# Hooly_2_023.net
KiCad netlist of a schematic drawn in EAGLE
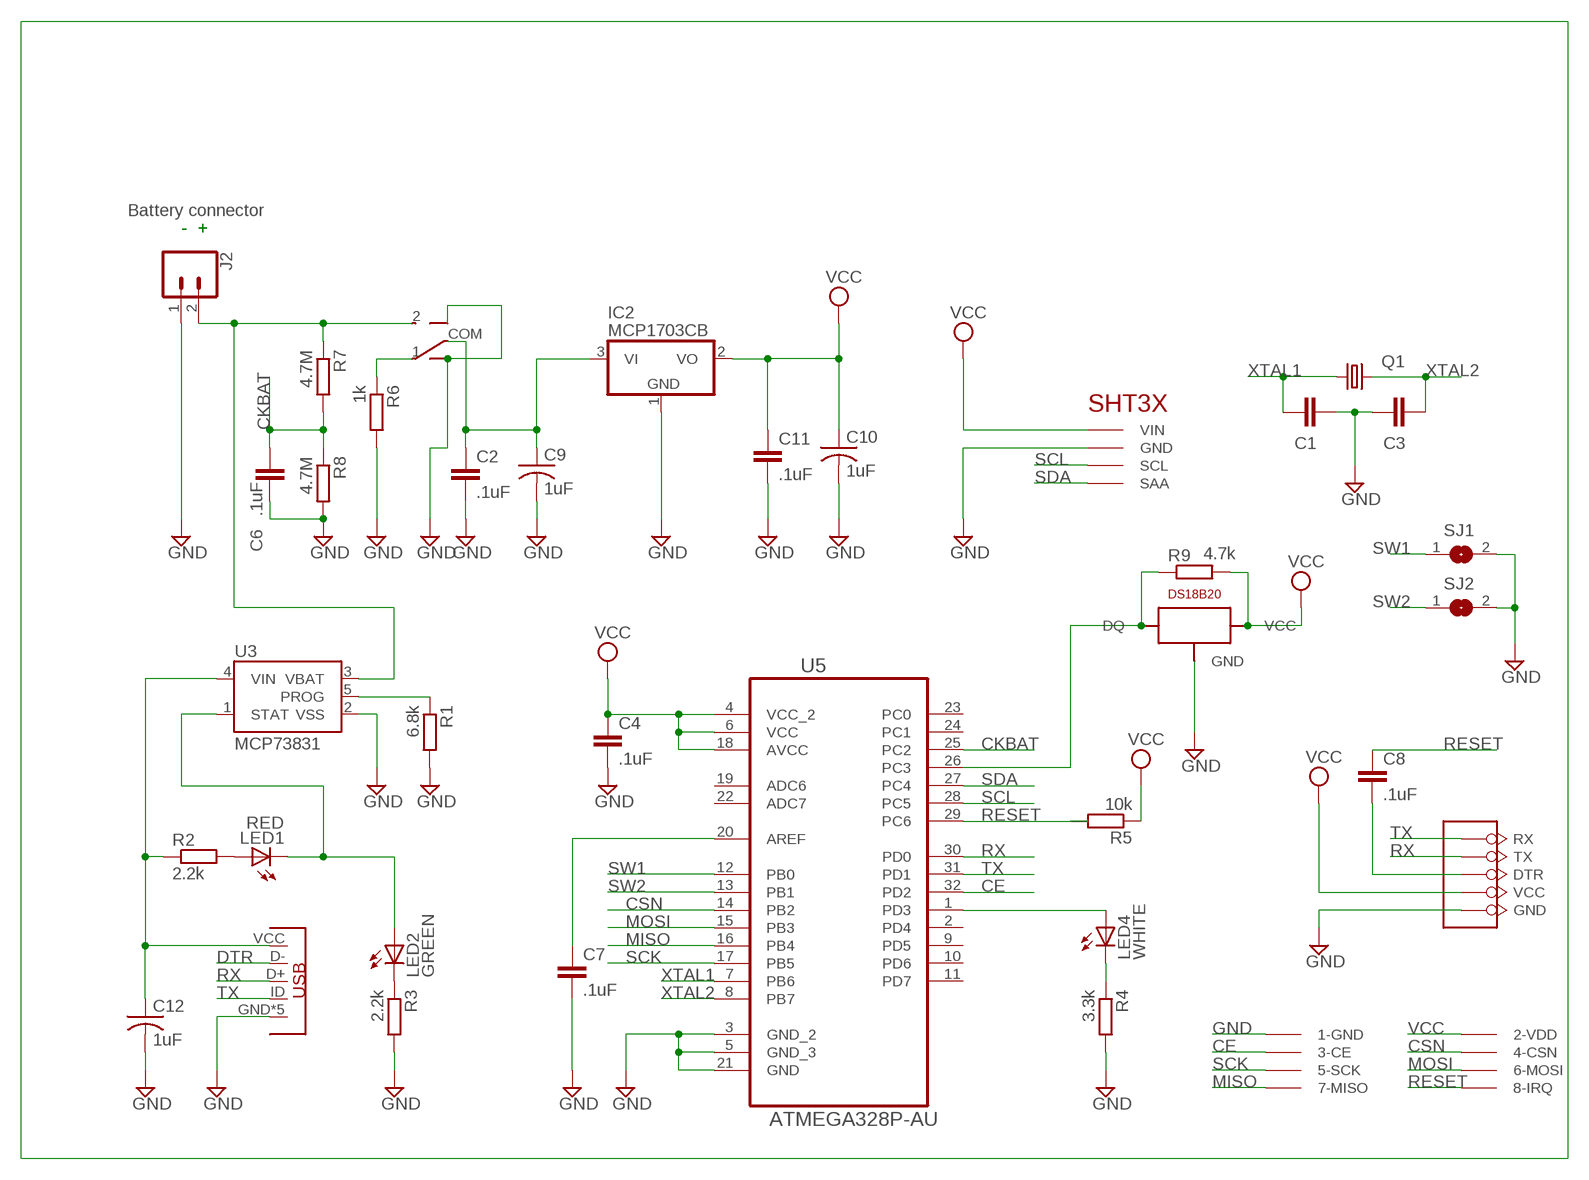
[diagram p0: schematic, sheet 1]

(export (version "E")
  (design (tool "Eeschema 10.0.6"))
  (components
    (comp (ref "C1")
      (value "C-EUC0603K")
      (footprint "eagle-import:C0603K")
      (libsource (lib "eagle-import") (part "C-EUC0603K"))
    )
    (comp (ref "C2")
      (value ".1uF")
      (footprint "eagle-import:C0603")
      (libsource (lib "eagle-import") (part "resistor_348_C-EUC0603"))
    )
    (comp (ref "C3")
      (value "C-EUC0603K")
      (footprint "eagle-import:C0603K")
      (libsource (lib "eagle-import") (part "C-EUC0603K"))
    )
    (comp (ref "C4")
      (value ".1uF")
      (footprint "eagle-import:C0603")
      (libsource (lib "eagle-import") (part "resistor_348_C-EUC0603"))
    )
    (comp (ref "C6")
      (value ".1uF")
      (footprint "eagle-import:C0603")
      (libsource (lib "eagle-import") (part "resistor_348_C-EUC0603"))
    )
    (comp (ref "C7")
      (value ".1uF")
      (footprint "eagle-import:C0603")
      (libsource (lib "eagle-import") (part "resistor_348_C-EUC0603"))
    )
    (comp (ref "C8")
      (value ".1uF")
      (footprint "eagle-import:C0603")
      (libsource (lib "eagle-import") (part "resistor_348_C-EUC0603"))
    )
    (comp (ref "C9")
      (value "1uF")
      (footprint "eagle-import:C1206K")
      (libsource (lib "eagle-import") (part "C-USC1206K"))
    )
    (comp (ref "C10")
      (value "1uF")
      (footprint "eagle-import:C1206K")
      (libsource (lib "eagle-import") (part "C-USC1206K"))
    )
    (comp (ref "C11")
      (value ".1uF")
      (footprint "eagle-import:C0603")
      (libsource (lib "eagle-import") (part "resistor_348_C-EUC0603"))
    )
    (comp (ref "C12")
      (value "1uF")
      (footprint "eagle-import:C1206K")
      (libsource (lib "eagle-import") (part "C-USC1206K"))
    )
    (comp (ref "IC2")
      (value "MCP1703CB")
      (footprint "eagle-import:SOT23")
      (libsource (lib "eagle-import") (part "MCP1703CB"))
    )
    (comp (ref "J2")
      (value "CONN_02")
      (footprint "eagle-import:1X02")
      (libsource (lib "eagle-import") (part "CONN_02"))
    )
    (comp (ref "LED1")
      (value "RED")
      (footprint "eagle-import:CHIPLED_0603")
      (libsource (lib "eagle-import") (part "LEDCHIPLED_0603"))
    )
    (comp (ref "LED2")
      (value "GREEN")
      (footprint "eagle-import:CHIPLED_0603")
      (libsource (lib "eagle-import") (part "LEDCHIPLED_0603"))
    )
    (comp (ref "LED4")
      (value "WHITE")
      (footprint "eagle-import:CHIPLED_0603")
      (libsource (lib "eagle-import") (part "LEDCHIPLED_0603"))
    )
    (comp (ref "Q1")
      (value "KX-9B")
      (footprint "eagle-import:5.0X3.2_2")
      (libsource (lib "eagle-import") (part "KX-9B"))
    )
    (comp (ref "R1")
      (value "6.8k")
      (footprint "eagle-import:R0603")
      (libsource (lib "eagle-import") (part "R-EU_R0603"))
    )
    (comp (ref "R2")
      (value "2.2k")
      (footprint "eagle-import:R0603")
      (libsource (lib "eagle-import") (part "R-EU_R0603"))
    )
    (comp (ref "R3")
      (value "2.2k")
      (footprint "eagle-import:R0603")
      (libsource (lib "eagle-import") (part "R-EU_R0603"))
    )
    (comp (ref "R4")
      (value "3.3k")
      (footprint "eagle-import:R0603")
      (libsource (lib "eagle-import") (part "R-EU_R0603"))
    )
    (comp (ref "R5")
      (value "10k")
      (footprint "eagle-import:R0603")
      (libsource (lib "eagle-import") (part "R-EU_R0603"))
    )
    (comp (ref "R6")
      (value "1k")
      (footprint "eagle-import:R0603")
      (libsource (lib "eagle-import") (part "R-EU_R0603"))
    )
    (comp (ref "R7")
      (value "4.7M")
      (footprint "eagle-import:R0603")
      (libsource (lib "eagle-import") (part "R-EU_R0603"))
    )
    (comp (ref "R8")
      (value "4.7M")
      (footprint "eagle-import:R0603")
      (libsource (lib "eagle-import") (part "R-EU_R0603"))
    )
    (comp (ref "R9")
      (value "4.7k")
      (footprint "eagle-import:R0603")
      (libsource (lib "eagle-import") (part "R-EU_R0603"))
    )
    (comp (ref "SJ1") (value "SJ") (footprint "eagle-import:SJ") (libsource (lib "eagle-import") (part "SJ")))
    (comp (ref "SJ2") (value "SJ") (footprint "eagle-import:SJ") (libsource (lib "eagle-import") (part "SJ")))
    (comp (ref "U$1")
      (value "SHT3XLARGE")
      (footprint "eagle-import:MYSHT3X")
      (libsource (lib "eagle-import") (part "SHT3XLARGE"))
    )
    (comp (ref "U$2")
      (value "MYSWITCH2MM")
      (footprint "eagle-import:MYSWITCH")
      (libsource (lib "eagle-import") (part "MYSWITCH2MM"))
    )
    (comp (ref "U$3")
      (value "MYDS18B20")
      (footprint "eagle-import:MYDS18B20")
      (libsource (lib "eagle-import") (part "MYDS18B20"))
    )
    (comp (ref "U$4")
      (value "MYNRF24L01SOCKET")
      (footprint "eagle-import:MYNRF24L01SOCKET")
      (libsource (lib "eagle-import") (part "MYNRF24L01SOCKET"))
    )
    (comp (ref "U$5")
      (value "FTDI232")
      (footprint "eagle-import:FTDI232")
      (libsource (lib "eagle-import") (part "FTDI232"))
    )
    (comp (ref "U$7")
      (value "MYMICROUSB")
      (footprint "eagle-import:MYMICROUSB")
      (libsource (lib "eagle-import") (part "MYMICROUSB"))
    )
    (comp (ref "U3")
      (value "MCP73831")
      (footprint "eagle-import:SOT23-5")
      (libsource (lib "eagle-import") (part "MCP73831"))
    )
    (comp (ref "U5")
      (value "ATMEGA328P-AU")
      (footprint "eagle-import:QFP80P900X900X120-32N")
      (libsource (lib "eagle-import") (part "ATMEGA328P-AU"))
    )
  )
  (nets
    (net (code "1") (name "/CE") (class "Default")
      (node (ref "U$4") (pin "CE") (pinfunction "3-CE_CE") (pintype "bidirectional"))
      (node (ref "U5") (pin "32") (pinfunction "PD2_32") (pintype "bidirectional"))
    )
    (net (code "2") (name "/CKBAT") (class "Default")
      (node (ref "C6") (pin "1") (pinfunction "1_1") (pintype "passive"))
      (node (ref "R7") (pin "2") (pinfunction "2_2") (pintype "passive"))
      (node (ref "R8") (pin "1") (pinfunction "1_1") (pintype "passive"))
      (node (ref "U5") (pin "25") (pinfunction "PC2_25") (pintype "bidirectional"))
    )
    (net (code "3") (name "/CSN") (class "Default")
      (node (ref "U$4") (pin "CSN") (pinfunction "4-CSN_CSN") (pintype "bidirectional"))
      (node (ref "U5") (pin "14") (pinfunction "PB2_14") (pintype "bidirectional"))
    )
    (net (code "4") (name "/DTR") (class "Default")
      (node (ref "C8") (pin "2") (pinfunction "2_2") (pintype "passive"))
      (node (ref "U$5") (pin "DTR") (pinfunction "DTR_DTR") (pintype "bidirectional"))
      (node (ref "U$7") (pin "D-") (pinfunction "D-_D-") (pintype "bidirectional"))
    )
    (net (code "5") (name "/MISO") (class "Default")
      (node (ref "U$4") (pin "MISO") (pinfunction "7-MISO_MISO") (pintype "bidirectional"))
      (node (ref "U5") (pin "16") (pinfunction "PB4_16") (pintype "bidirectional"))
    )
    (net (code "6") (name "/MOSI") (class "Default")
      (node (ref "U$4") (pin "MOSI") (pinfunction "6-MOSI_MOSI") (pintype "bidirectional"))
      (node (ref "U5") (pin "15") (pinfunction "PB3_15") (pintype "bidirectional"))
    )
    (net (code "7") (name "/RESET") (class "Default")
      (node (ref "C8") (pin "1") (pinfunction "1_1") (pintype "passive"))
      (node (ref "R5") (pin "2") (pinfunction "2_2") (pintype "passive"))
      (node (ref "U$4") (pin "IRQ") (pinfunction "8-IRQ_IRQ") (pintype "bidirectional"))
      (node (ref "U5") (pin "29") (pinfunction "PC6_29") (pintype "bidirectional"))
    )
    (net (code "8") (name "/RX") (class "Default")
      (node (ref "U$5") (pin "TX") (pinfunction "TX_TX") (pintype "bidirectional"))
      (node (ref "U$7") (pin "D+") (pinfunction "D+_D+") (pintype "bidirectional"))
      (node (ref "U5") (pin "30") (pinfunction "PD0_30") (pintype "bidirectional"))
    )
    (net (code "9") (name "/SCK") (class "Default")
      (node (ref "U$4") (pin "SCK") (pinfunction "5-SCK_SCK") (pintype "bidirectional"))
      (node (ref "U5") (pin "17") (pinfunction "PB5_17") (pintype "bidirectional"))
    )
    (net (code "10") (name "/SCL") (class "Default")
      (node (ref "U$1") (pin "SCL") (pinfunction "SCL_SCL") (pintype "bidirectional"))
      (node (ref "U5") (pin "28") (pinfunction "PC5_28") (pintype "bidirectional"))
    )
    (net (code "11") (name "/SDA") (class "Default")
      (node (ref "U$1") (pin "SAA") (pinfunction "SAA_SAA") (pintype "bidirectional"))
      (node (ref "U5") (pin "27") (pinfunction "PC4_27") (pintype "bidirectional"))
    )
    (net (code "12") (name "/SW1") (class "Default")
      (node (ref "SJ1") (pin "1") (pinfunction "1_1") (pintype "passive"))
      (node (ref "U5") (pin "12") (pinfunction "PB0_12") (pintype "bidirectional"))
    )
    (net (code "13") (name "/SW2") (class "Default")
      (node (ref "SJ2") (pin "1") (pinfunction "1_1") (pintype "passive"))
      (node (ref "U5") (pin "13") (pinfunction "PB1_13") (pintype "bidirectional"))
    )
    (net (code "14") (name "/TX") (class "Default")
      (node (ref "U$5") (pin "RX") (pinfunction "RX_RX") (pintype "bidirectional"))
      (node (ref "U$7") (pin "ID") (pinfunction "ID_ID") (pintype "bidirectional"))
      (node (ref "U5") (pin "31") (pinfunction "PD1_31") (pintype "bidirectional"))
    )
    (net (code "15") (name "/XTAL1") (class "Default")
      (node (ref "C1") (pin "1") (pinfunction "1_1") (pintype "passive"))
      (node (ref "Q1") (pin "1") (pinfunction "1_1") (pintype "passive"))
      (node (ref "U5") (pin "7") (pinfunction "PB6_7") (pintype "bidirectional"))
    )
    (net (code "16") (name "/XTAL2") (class "Default")
      (node (ref "C3") (pin "2") (pinfunction "2_2") (pintype "passive"))
      (node (ref "Q1") (pin "2") (pinfunction "2_2") (pintype "passive"))
      (node (ref "U5") (pin "8") (pinfunction "PB7_8") (pintype "bidirectional"))
    )
    (net (code "17") (name "GND") (class "Default")
      (node (ref "C1") (pin "2") (pinfunction "2_2") (pintype "passive"))
      (node (ref "C10") (pin "2") (pinfunction "2_2") (pintype "passive"))
      (node (ref "C11") (pin "2") (pinfunction "2_2") (pintype "passive"))
      (node (ref "C12") (pin "2") (pinfunction "2_2") (pintype "passive"))
      (node (ref "C2") (pin "2") (pinfunction "2_2") (pintype "passive"))
      (node (ref "C3") (pin "1") (pinfunction "1_1") (pintype "passive"))
      (node (ref "C4") (pin "2") (pinfunction "2_2") (pintype "passive"))
      (node (ref "C6") (pin "2") (pinfunction "2_2") (pintype "passive"))
      (node (ref "C7") (pin "2") (pinfunction "2_2") (pintype "passive"))
      (node (ref "C9") (pin "2") (pinfunction "2_2") (pintype "passive"))
      (node (ref "IC2") (pin "1") (pinfunction "GND_1") (pintype "passive"))
      (node (ref "J2") (pin "1") (pinfunction "1_1") (pintype "passive"))
      (node (ref "R1") (pin "2") (pinfunction "2_2") (pintype "passive"))
      (node (ref "R3") (pin "2") (pinfunction "2_2") (pintype "passive"))
      (node (ref "R4") (pin "2") (pinfunction "2_2") (pintype "passive"))
      (node (ref "R6") (pin "2") (pinfunction "2_2") (pintype "passive"))
      (node (ref "R8") (pin "2") (pinfunction "2_2") (pintype "passive"))
      (node (ref "SJ1") (pin "2") (pinfunction "2_2") (pintype "passive"))
      (node (ref "SJ2") (pin "2") (pinfunction "2_2") (pintype "passive"))
      (node (ref "U$1") (pin "GND") (pinfunction "GND_GND") (pintype "bidirectional"))
      (node (ref "U$2") (pin "GND1") (pinfunction "GND1_GND1") (pintype "bidirectional"))
      (node (ref "U$2") (pin "GND2") (pinfunction "GND2_GND2") (pintype "bidirectional"))
      (node (ref "U$3") (pin "GND") (pinfunction "GND_GND") (pintype "bidirectional"))
      (node (ref "U$4") (pin "GND") (pinfunction "1-GND_GND") (pintype "bidirectional"))
      (node (ref "U$5") (pin "GND") (pinfunction "GND_GND") (pintype "bidirectional"))
      (node (ref "U$7") (pin "GND") (pinfunction "GND_GND") (pintype "bidirectional"))
      (node (ref "U$7") (pin "P$6") (pinfunction "GND_P$6") (pintype "bidirectional"))
      (node (ref "U$7") (pin "P$7") (pinfunction "GND_P$7") (pintype "bidirectional"))
      (node (ref "U$7") (pin "P$8") (pinfunction "GND_P$8") (pintype "bidirectional"))
      (node (ref "U$7") (pin "P$9") (pinfunction "GND_P$9") (pintype "bidirectional"))
      (node (ref "U3") (pin "2") (pinfunction "VSS_2") (pintype "power_in"))
      (node (ref "U5") (pin "21") (pinfunction "GND_21") (pintype "passive"))
      (node (ref "U5") (pin "3") (pinfunction "GND_2_3") (pintype "passive"))
      (node (ref "U5") (pin "5") (pinfunction "GND_3_5") (pintype "passive"))
    )
    (net (code "18") (name "Net-(IC2-VI)") (class "Default")
      (node (ref "C2") (pin "1") (pinfunction "1_1") (pintype "passive"))
      (node (ref "C9") (pin "1") (pinfunction "1_1") (pintype "passive"))
      (node (ref "IC2") (pin "3") (pinfunction "VI_3") (pintype "input"))
      (node (ref "U$2") (pin "COM") (pinfunction "COM_COM") (pintype "bidirectional"))
    )
    (net (code "19") (name "Net-(LED1-PadA)") (class "Default")
      (node (ref "LED1") (pin "A") (pinfunction "A_A") (pintype "passive"))
      (node (ref "R2") (pin "2") (pinfunction "2_2") (pintype "passive"))
    )
    (net (code "20") (name "Net-(LED2-PadC)") (class "Default")
      (node (ref "LED2") (pin "C") (pinfunction "C_C") (pintype "passive"))
      (node (ref "R3") (pin "1") (pinfunction "1_1") (pintype "passive"))
    )
    (net (code "21") (name "Net-(LED4-PadC)") (class "Default")
      (node (ref "LED4") (pin "C") (pinfunction "C_C") (pintype "passive"))
      (node (ref "R4") (pin "1") (pinfunction "1_1") (pintype "passive"))
    )
    (net (code "22") (name "Net-(R6-Pad1)") (class "Default")
      (node (ref "R6") (pin "1") (pinfunction "1_1") (pintype "passive"))
      (node (ref "U$2") (pin "1") (pinfunction "1_1") (pintype "bidirectional"))
    )
    (net (code "23") (name "Net-(U3-PROG)") (class "Default")
      (node (ref "R1") (pin "1") (pinfunction "1_1") (pintype "passive"))
      (node (ref "U3") (pin "5") (pinfunction "PROG_5") (pintype "input"))
    )
    (net (code "24") (name "Net-(U3-STAT)") (class "Default")
      (node (ref "LED1") (pin "C") (pinfunction "C_C") (pintype "passive"))
      (node (ref "LED2") (pin "A") (pinfunction "A_A") (pintype "passive"))
      (node (ref "U3") (pin "1") (pinfunction "STAT_1") (pintype "output"))
    )
    (net (code "25") (name "Net-(U3-VBAT)") (class "Default")
      (node (ref "J2") (pin "2") (pinfunction "2_2") (pintype "passive"))
      (node (ref "R7") (pin "1") (pinfunction "1_1") (pintype "passive"))
      (node (ref "U$2") (pin "2") (pinfunction "2_2") (pintype "bidirectional"))
      (node (ref "U3") (pin "3") (pinfunction "VBAT_3") (pintype "power_in"))
    )
    (net (code "26") (name "Net-(U3-VIN)") (class "Default")
      (node (ref "C12") (pin "1") (pinfunction "1_1") (pintype "passive"))
      (node (ref "R2") (pin "1") (pinfunction "1_1") (pintype "passive"))
      (node (ref "U$7") (pin "VCC") (pinfunction "VCC_VCC") (pintype "bidirectional"))
      (node (ref "U3") (pin "4") (pinfunction "VIN_4") (pintype "power_in"))
    )
    (net (code "27") (name "Net-(U5-AREF)") (class "Default")
      (node (ref "C7") (pin "1") (pinfunction "1_1") (pintype "passive"))
      (node (ref "U5") (pin "20") (pinfunction "AREF_20") (pintype "input"))
    )
    (net (code "28") (name "Net-(U5-PC3)") (class "Default")
      (node (ref "R9") (pin "1") (pinfunction "1_1") (pintype "passive"))
      (node (ref "U$3") (pin "DQ") (pinfunction "DQ_DQ") (pintype "bidirectional"))
      (node (ref "U5") (pin "26") (pinfunction "PC3_26") (pintype "bidirectional"))
    )
    (net (code "29") (name "Net-(U5-PD3)") (class "Default")
      (node (ref "LED4") (pin "A") (pinfunction "A_A") (pintype "passive"))
      (node (ref "U5") (pin "1") (pinfunction "PD3_1") (pintype "bidirectional"))
    )
    (net (code "30") (name "VCC") (class "Default")
      (node (ref "C10") (pin "1") (pinfunction "1_1") (pintype "passive"))
      (node (ref "C11") (pin "1") (pinfunction "1_1") (pintype "passive"))
      (node (ref "C4") (pin "1") (pinfunction "1_1") (pintype "passive"))
      (node (ref "IC2") (pin "2") (pinfunction "VO_2") (pintype "passive"))
      (node (ref "R5") (pin "1") (pinfunction "1_1") (pintype "passive"))
      (node (ref "R9") (pin "2") (pinfunction "2_2") (pintype "passive"))
      (node (ref "U$1") (pin "VIN") (pinfunction "VIN_VIN") (pintype "bidirectional"))
      (node (ref "U$3") (pin "VCC") (pinfunction "VCC_VCC") (pintype "bidirectional"))
      (node (ref "U$4") (pin "VDD") (pinfunction "2-VDD_VDD") (pintype "bidirectional"))
      (node (ref "U$5") (pin "VCC") (pinfunction "VCC_VCC") (pintype "bidirectional"))
      (node (ref "U5") (pin "18") (pinfunction "AVCC_18") (pintype "power_in"))
      (node (ref "U5") (pin "4") (pinfunction "VCC_2_4") (pintype "power_in"))
      (node (ref "U5") (pin "6") (pinfunction "VCC_6") (pintype "power_in"))
    )
    (net (code "31") (name "unconnected-(U5-ADC6-Pad19)") (class "Default")
      (node (ref "U5") (pin "19") (pinfunction "ADC6_19") (pintype "input"))
    )
    (net (code "32") (name "unconnected-(U5-ADC7-Pad22)") (class "Default")
      (node (ref "U5") (pin "22") (pinfunction "ADC7_22") (pintype "input"))
    )
    (net (code "33") (name "unconnected-(U5-PC0-Pad23)") (class "Default")
      (node (ref "U5") (pin "23") (pinfunction "PC0_23") (pintype "bidirectional"))
    )
    (net (code "34") (name "unconnected-(U5-PC1-Pad24)") (class "Default")
      (node (ref "U5") (pin "24") (pinfunction "PC1_24") (pintype "bidirectional"))
    )
    (net (code "35") (name "unconnected-(U5-PD4-Pad2)") (class "Default")
      (node (ref "U5") (pin "2") (pinfunction "PD4_2") (pintype "bidirectional"))
    )
    (net (code "36") (name "unconnected-(U5-PD5-Pad9)") (class "Default")
      (node (ref "U5") (pin "9") (pinfunction "PD5_9") (pintype "bidirectional"))
    )
    (net (code "37") (name "unconnected-(U5-PD6-Pad10)") (class "Default")
      (node (ref "U5") (pin "10") (pinfunction "PD6_10") (pintype "bidirectional"))
    )
    (net (code "38") (name "unconnected-(U5-PD7-Pad11)") (class "Default")
      (node (ref "U5") (pin "11") (pinfunction "PD7_11") (pintype "bidirectional"))
    )
  )
)
